# FuseBox_ECU_R3.net
KiCad netlist of a schematic drawn in EAGLE
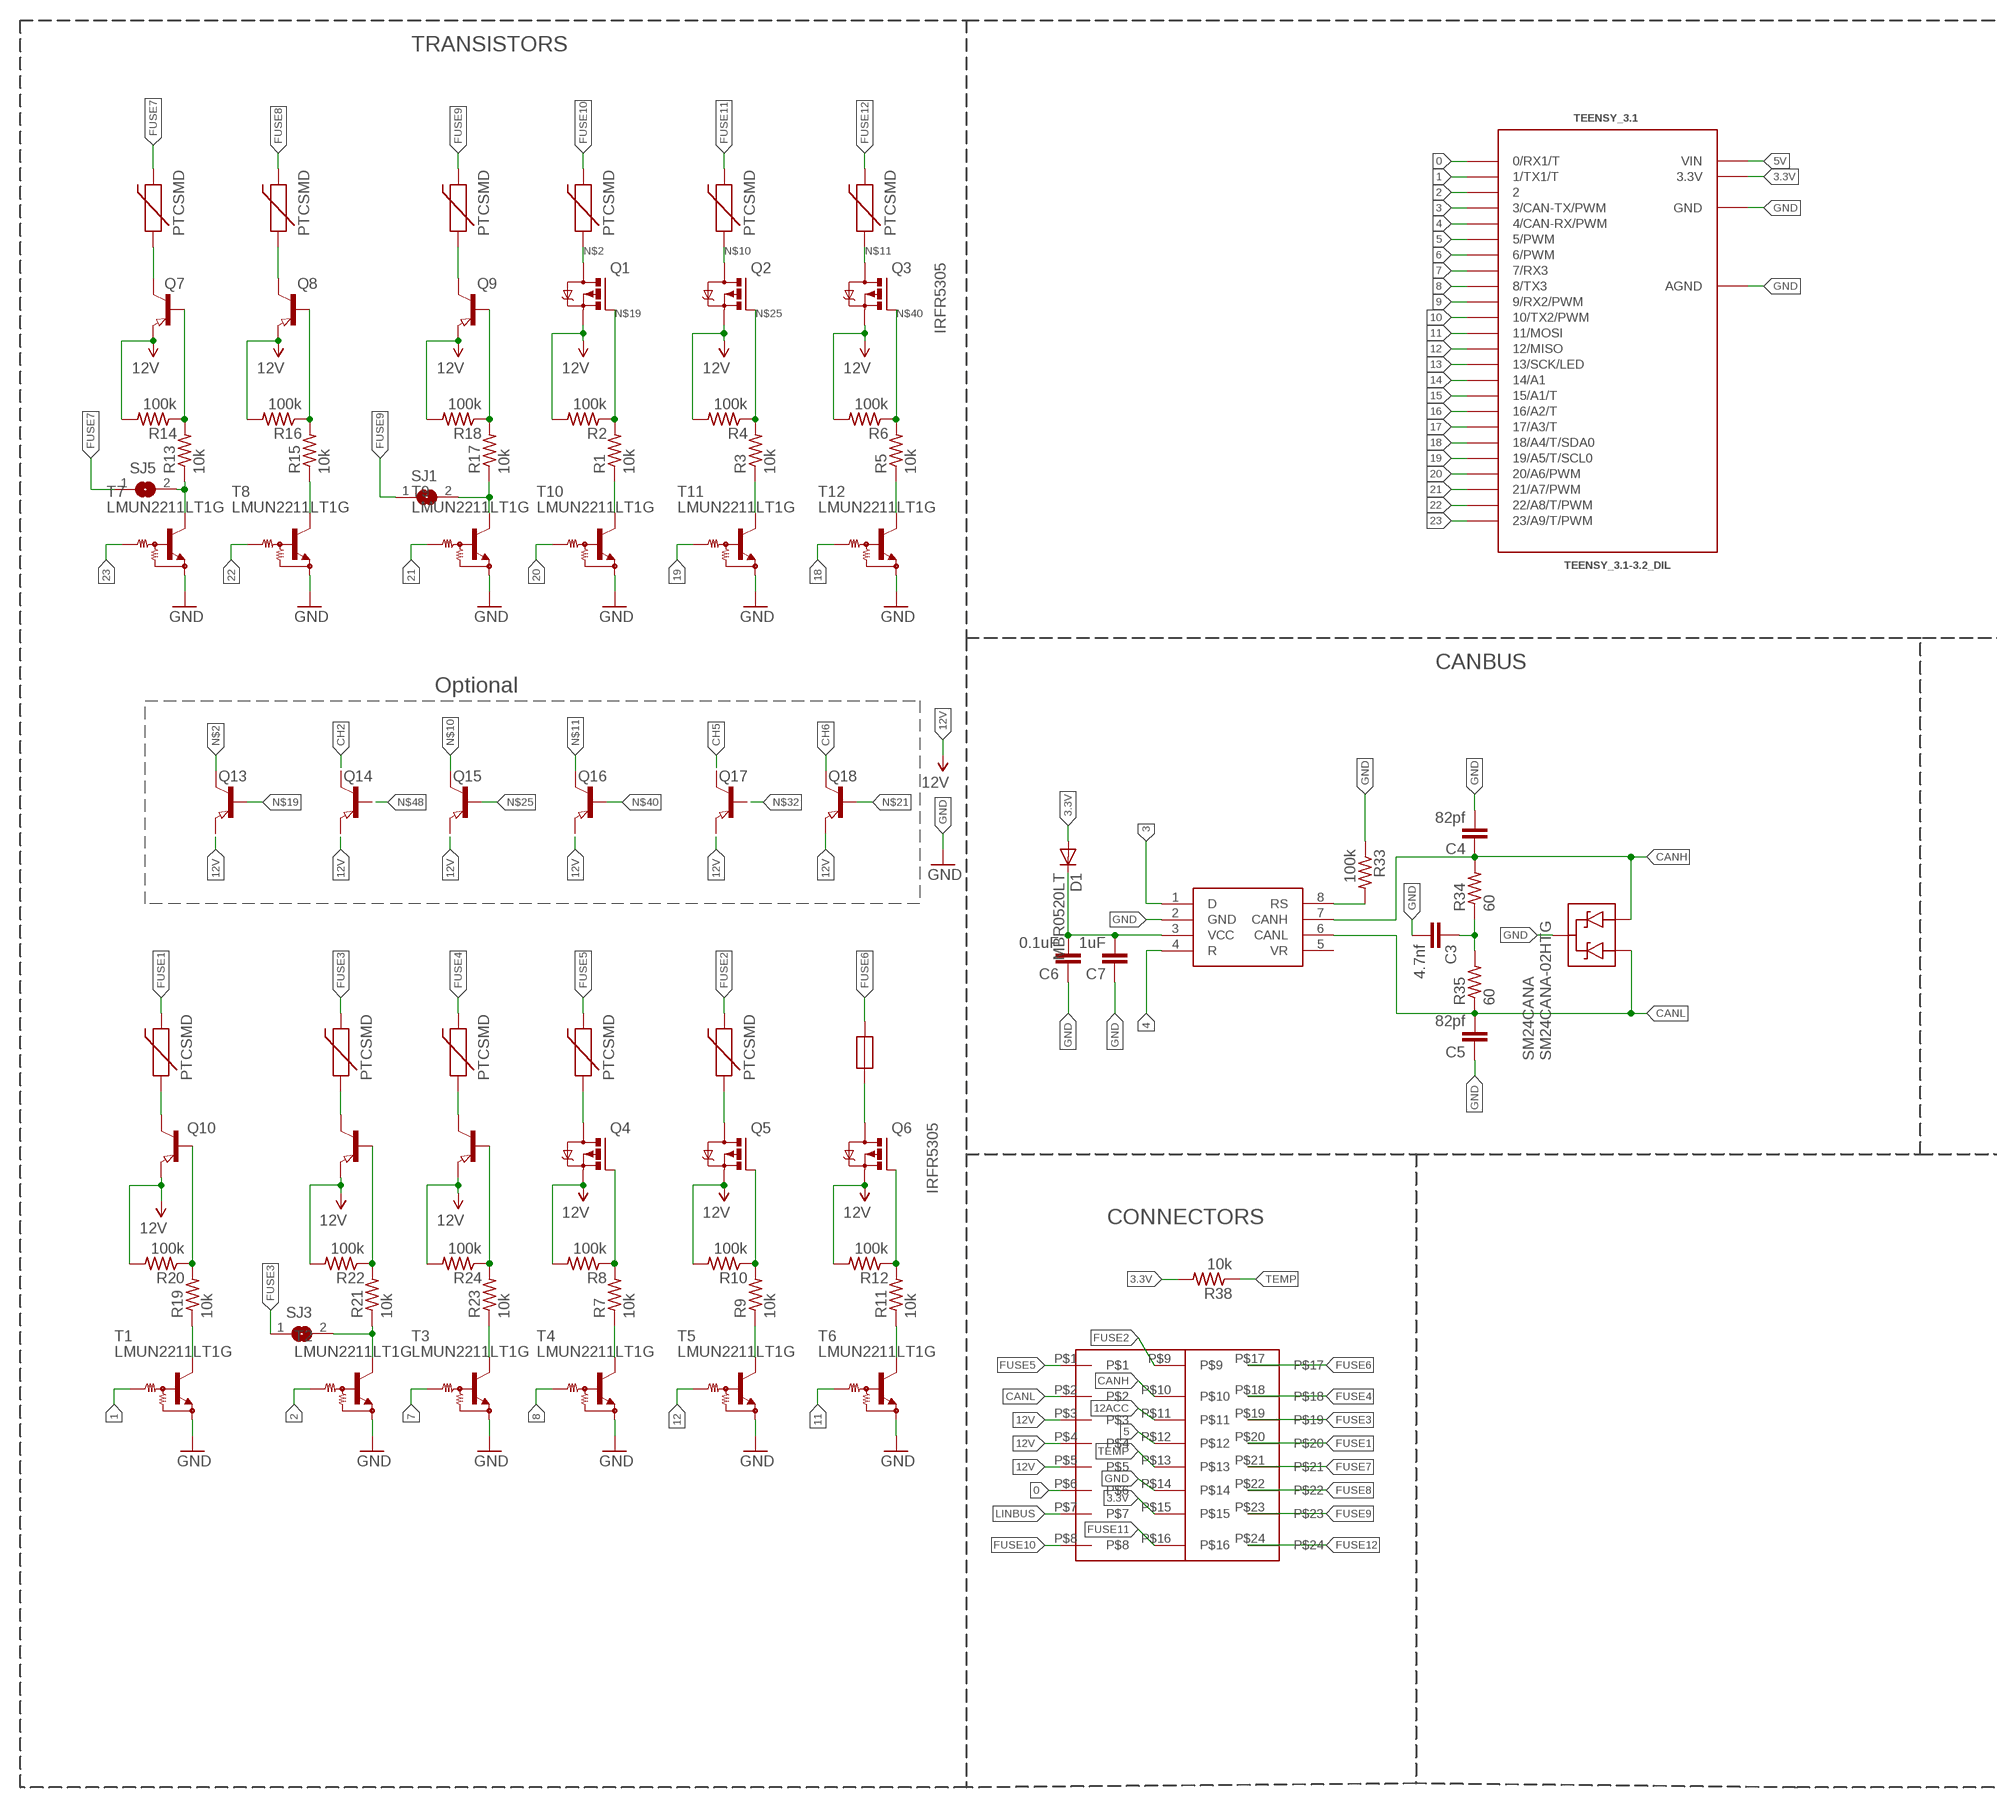
[diagram p0: schematic, sheet 1, part 1 of 2]
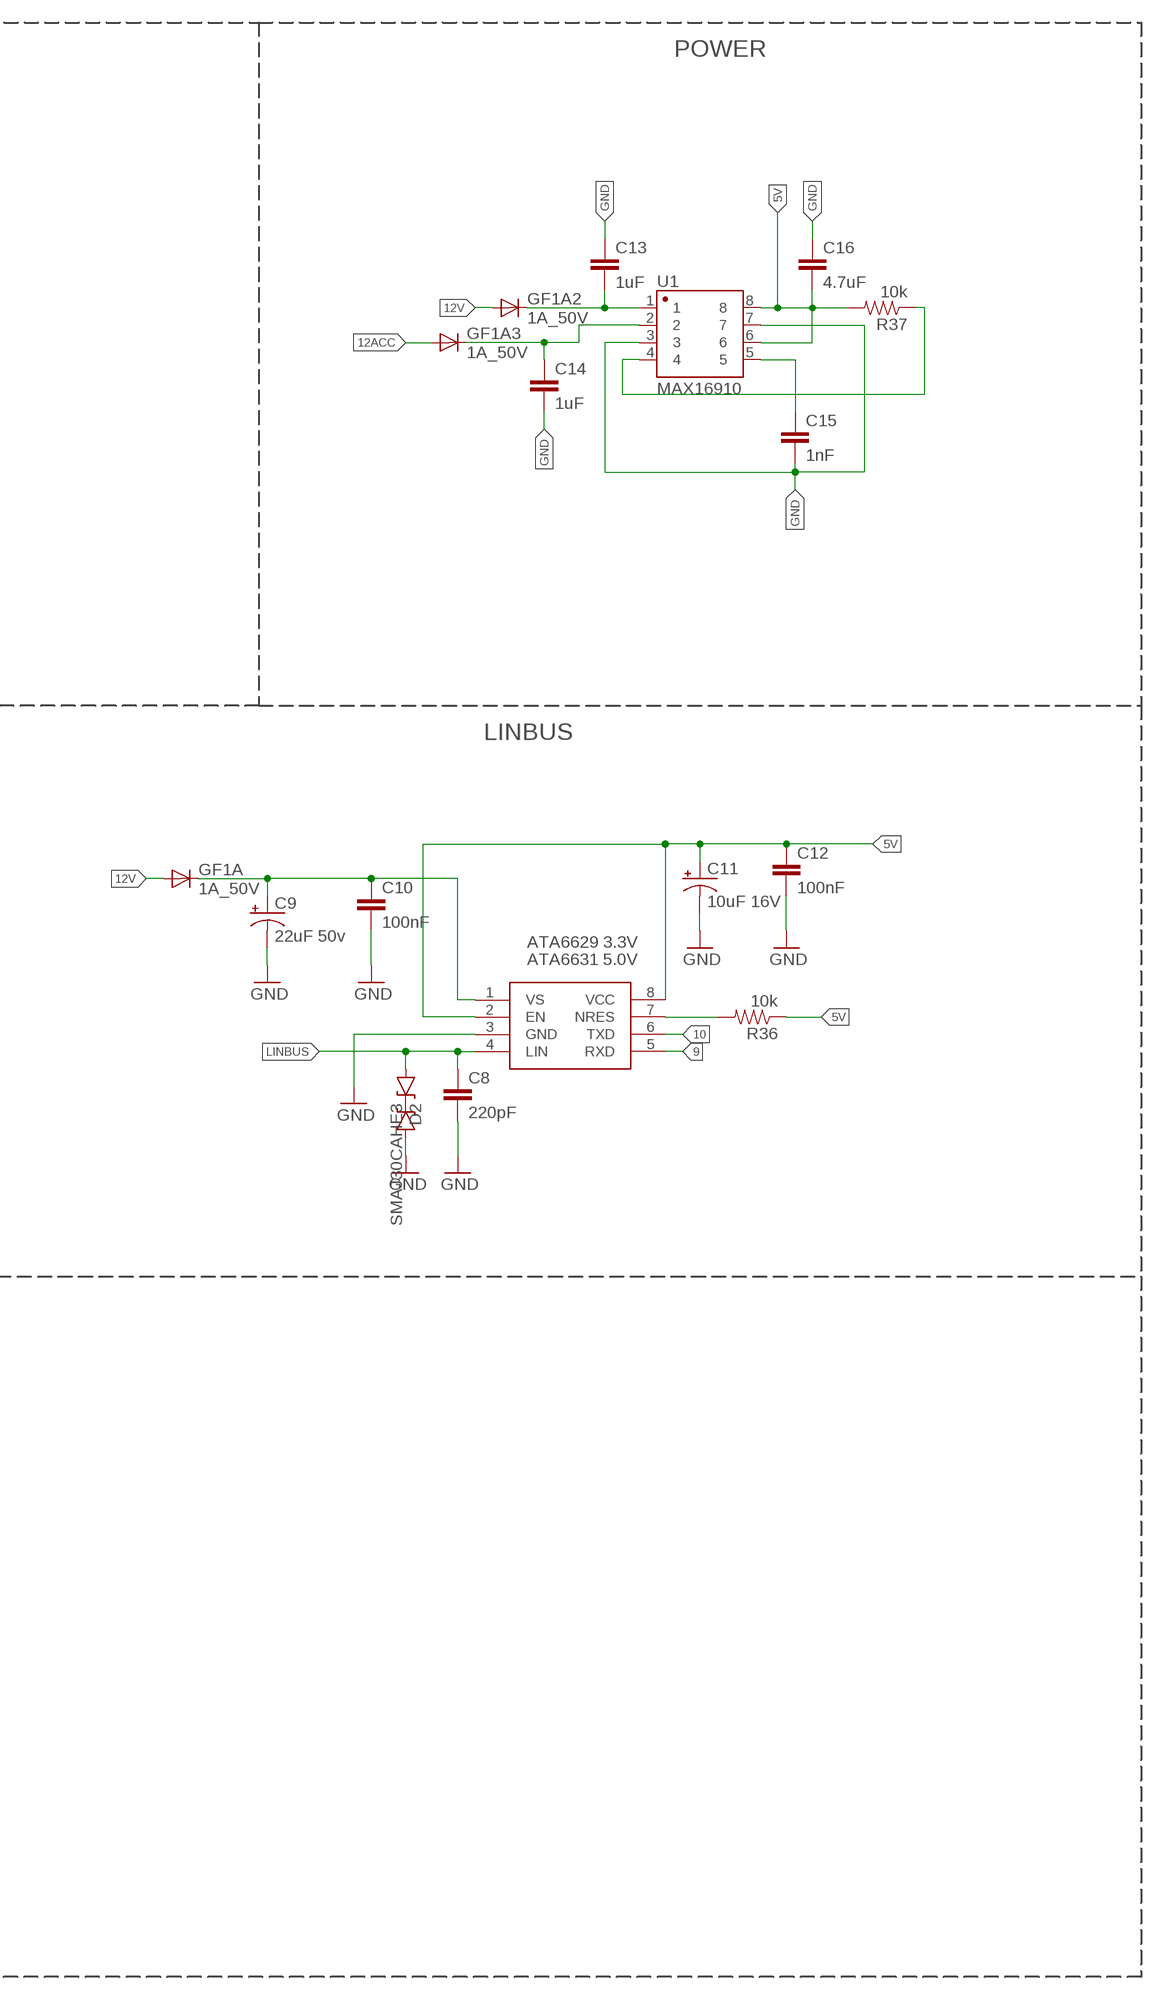
[diagram p1: schematic, sheet 1, part 2 of 2]

(export (version "E")
  (design (tool "Eeschema 10.0.6"))
  (components
    (comp (ref "ATA6631")
      (value "ATA6631")
      (footprint "eagle-import:S08")
      (libsource (lib "eagle-import") (part "ATA6631"))
    )
    (comp (ref "C3")
      (value "4.7nf")
      (footprint "eagle-import:0603-CAP")
      (libsource (lib "eagle-import") (part "SparkFun-Capacitors_CAP0603-CAP"))
    )
    (comp (ref "C4")
      (value "82pf")
      (footprint "eagle-import:0603-CAP")
      (libsource (lib "eagle-import") (part "SparkFun-Capacitors_CAP0603-CAP"))
    )
    (comp (ref "C5")
      (value "82pf")
      (footprint "eagle-import:0603-CAP")
      (libsource (lib "eagle-import") (part "SparkFun-Capacitors_CAP0603-CAP"))
    )
    (comp (ref "C6")
      (value "0.1uF")
      (footprint "eagle-import:0603-CAP")
      (libsource (lib "eagle-import") (part "SparkFun-Capacitors_CAP0603-CAP"))
    )
    (comp (ref "C7")
      (value "1uF")
      (footprint "eagle-import:0603-CAP")
      (libsource (lib "eagle-import") (part "SparkFun-Capacitors_CAP0603-CAP"))
    )
    (comp (ref "C8")
      (value "220pF")
      (footprint "eagle-import:0603-CAP")
      (libsource (lib "eagle-import") (part "SparkFun-Capacitors_CAP0603-CAP"))
    )
    (comp (ref "C9")
      (value "22uF 50v")
      (footprint "eagle-import:PANASONIC_D")
      (libsource (lib "eagle-import") (part "SparkFun-Capacitors_CAP_POLD"))
    )
    (comp (ref "C10")
      (value "100nF")
      (footprint "eagle-import:0603-CAP")
      (libsource (lib "eagle-import") (part "SparkFun-Capacitors_CAP0603-CAP"))
    )
    (comp (ref "C11")
      (value "10uF 16V")
      (footprint "eagle-import:EIA3216")
      (libsource (lib "eagle-import") (part "CAP_POL1206"))
    )
    (comp (ref "C12")
      (value "100nF")
      (footprint "eagle-import:0603-CAP")
      (libsource (lib "eagle-import") (part "SparkFun-Capacitors_CAP0603-CAP"))
    )
    (comp (ref "C13")
      (value "1uF")
      (footprint "eagle-import:0805")
      (libsource (lib "eagle-import") (part "CAP0805"))
    )
    (comp (ref "C14")
      (value "1uF")
      (footprint "eagle-import:0805")
      (libsource (lib "eagle-import") (part "CAP0805"))
    )
    (comp (ref "C15")
      (value "1nF")
      (footprint "eagle-import:0805")
      (libsource (lib "eagle-import") (part "CAP0805"))
    )
    (comp (ref "C16")
      (value "4.7uF")
      (footprint "eagle-import:0805")
      (libsource (lib "eagle-import") (part "CAP0805"))
    )
    (comp (ref "D1")
      (value "MBR0520LT")
      (footprint "eagle-import:SOD123")
      (libsource (lib "eagle-import") (part "MBR0520LT"))
    )
    (comp (ref "D2")
      (value "SMAJ30CAHE3")
      (footprint "eagle-import:SMA-DIODE")
      (libsource (lib "eagle-import") (part "SMAJ30CAHE3"))
    )
    (comp (ref "F1")
      (value "PTCSMD")
      (footprint "eagle-import:PTC-1206")
      (libsource (lib "eagle-import") (part "PTCSMD"))
    )
    (comp (ref "F2")
      (value "PTCSMD")
      (footprint "eagle-import:PTC-1206")
      (libsource (lib "eagle-import") (part "PTCSMD"))
    )
    (comp (ref "F3")
      (value "PTCSMD")
      (footprint "eagle-import:PTC-1206")
      (libsource (lib "eagle-import") (part "PTCSMD"))
    )
    (comp (ref "F4")
      (value "PTCSMD")
      (footprint "eagle-import:PTC-1206")
      (libsource (lib "eagle-import") (part "PTCSMD"))
    )
    (comp (ref "F5")
      (value "PTCSMD")
      (footprint "eagle-import:PTC-1206")
      (libsource (lib "eagle-import") (part "PTCSMD"))
    )
    (comp (ref "F6")
      (value "PTCSMD")
      (footprint "eagle-import:PTC-1206")
      (libsource (lib "eagle-import") (part "PTCSMD"))
    )
    (comp (ref "F7")
      (value "PTCSMD")
      (footprint "eagle-import:PTC-1206")
      (libsource (lib "eagle-import") (part "PTCSMD"))
    )
    (comp (ref "F8")
      (value "PTCSMD")
      (footprint "eagle-import:PTC-1206")
      (libsource (lib "eagle-import") (part "PTCSMD"))
    )
    (comp (ref "F9")
      (value "PTCSMD")
      (footprint "eagle-import:PTC-1206")
      (libsource (lib "eagle-import") (part "PTCSMD"))
    )
    (comp (ref "F10")
      (value "PTCSMD")
      (footprint "eagle-import:PTC-1206")
      (libsource (lib "eagle-import") (part "PTCSMD"))
    )
    (comp (ref "F11")
      (value "PTCSMD")
      (footprint "eagle-import:PTC-1206")
      (libsource (lib "eagle-import") (part "PTCSMD"))
    )
    (comp (ref "GF1A")
      (value "1A_50V")
      (footprint "eagle-import:DO-214AC")
      (libsource (lib "eagle-import") (part "DIODE-DO-214AC"))
    )
    (comp (ref "GF1A2")
      (value "1A_50V")
      (footprint "eagle-import:DO-214AC")
      (libsource (lib "eagle-import") (part "DIODE-DO-214AC"))
    )
    (comp (ref "GF1A3")
      (value "1A_50V")
      (footprint "eagle-import:DO-214AC")
      (libsource (lib "eagle-import") (part "DIODE-DO-214AC"))
    )
    (comp (ref "Q1")
      (value "IRFR5305")
      (footprint "eagle-import:D-PAK_TO252AA")
      (libsource (lib "eagle-import") (part "IRF?5305R"))
    )
    (comp (ref "Q2")
      (value "IRFR5305")
      (footprint "eagle-import:D-PAK_TO252AA")
      (libsource (lib "eagle-import") (part "IRF?5305R"))
    )
    (comp (ref "Q3")
      (value "IRFR5305")
      (footprint "eagle-import:D-PAK_TO252AA")
      (libsource (lib "eagle-import") (part "IRF?5305R"))
    )
    (comp (ref "Q4")
      (value "IRFR5305")
      (footprint "eagle-import:D-PAK_TO252AA")
      (libsource (lib "eagle-import") (part "IRF?5305R"))
    )
    (comp (ref "Q5")
      (value "IRFR5305")
      (footprint "eagle-import:D-PAK_TO252AA")
      (libsource (lib "eagle-import") (part "IRF?5305R"))
    )
    (comp (ref "Q6")
      (value "IRFR5305")
      (footprint "eagle-import:D-PAK_TO252AA")
      (libsource (lib "eagle-import") (part "IRF?5305R"))
    )
    (comp (ref "Q7")
      (value "PNP-TRANSISTOR_SOT23")
      (footprint "eagle-import:SOT23")
      (libsource (lib "eagle-import") (part "PNP-TRANSISTOR_SOT23"))
    )
    (comp (ref "Q8")
      (value "PNP-TRANSISTOR_SOT23")
      (footprint "eagle-import:SOT23")
      (libsource (lib "eagle-import") (part "PNP-TRANSISTOR_SOT23"))
    )
    (comp (ref "Q9")
      (value "PNP-TRANSISTOR_SOT23")
      (footprint "eagle-import:SOT23")
      (libsource (lib "eagle-import") (part "PNP-TRANSISTOR_SOT23"))
    )
    (comp (ref "Q10")
      (value "PNP-TRANSISTOR_SOT23")
      (footprint "eagle-import:SOT23")
      (libsource (lib "eagle-import") (part "PNP-TRANSISTOR_SOT23"))
    )
    (comp (ref "Q11")
      (value "PNP-TRANSISTOR_SOT23")
      (footprint "eagle-import:SOT23")
      (libsource (lib "eagle-import") (part "PNP-TRANSISTOR_SOT23"))
    )
    (comp (ref "Q12")
      (value "PNP-TRANSISTOR_SOT23")
      (footprint "eagle-import:SOT23")
      (libsource (lib "eagle-import") (part "PNP-TRANSISTOR_SOT23"))
    )
    (comp (ref "Q13")
      (value "PNP-TRANSISTOR_SOT23")
      (footprint "eagle-import:SOT23")
      (libsource (lib "eagle-import") (part "PNP-TRANSISTOR_SOT23"))
    )
    (comp (ref "Q14")
      (value "PNP-TRANSISTOR_SOT23")
      (footprint "eagle-import:SOT23")
      (libsource (lib "eagle-import") (part "PNP-TRANSISTOR_SOT23"))
    )
    (comp (ref "Q15")
      (value "PNP-TRANSISTOR_SOT23")
      (footprint "eagle-import:SOT23")
      (libsource (lib "eagle-import") (part "PNP-TRANSISTOR_SOT23"))
    )
    (comp (ref "Q16")
      (value "PNP-TRANSISTOR_SOT23")
      (footprint "eagle-import:SOT23")
      (libsource (lib "eagle-import") (part "PNP-TRANSISTOR_SOT23"))
    )
    (comp (ref "Q17")
      (value "PNP-TRANSISTOR_SOT23")
      (footprint "eagle-import:SOT23")
      (libsource (lib "eagle-import") (part "PNP-TRANSISTOR_SOT23"))
    )
    (comp (ref "Q18")
      (value "PNP-TRANSISTOR_SOT23")
      (footprint "eagle-import:SOT23")
      (libsource (lib "eagle-import") (part "PNP-TRANSISTOR_SOT23"))
    )
    (comp (ref "R1")
      (value "10k")
      (footprint "eagle-import:R0402")
      (libsource (lib "eagle-import") (part "R-US_R0402"))
    )
    (comp (ref "R2")
      (value "100k")
      (footprint "eagle-import:R0402")
      (libsource (lib "eagle-import") (part "R-US_R0402"))
    )
    (comp (ref "R3")
      (value "10k")
      (footprint "eagle-import:R0402")
      (libsource (lib "eagle-import") (part "R-US_R0402"))
    )
    (comp (ref "R4")
      (value "100k")
      (footprint "eagle-import:R0402")
      (libsource (lib "eagle-import") (part "R-US_R0402"))
    )
    (comp (ref "R5")
      (value "10k")
      (footprint "eagle-import:R0402")
      (libsource (lib "eagle-import") (part "R-US_R0402"))
    )
    (comp (ref "R6")
      (value "100k")
      (footprint "eagle-import:R0402")
      (libsource (lib "eagle-import") (part "R-US_R0402"))
    )
    (comp (ref "R7")
      (value "10k")
      (footprint "eagle-import:R0402")
      (libsource (lib "eagle-import") (part "R-US_R0402"))
    )
    (comp (ref "R8")
      (value "100k")
      (footprint "eagle-import:R0402")
      (libsource (lib "eagle-import") (part "R-US_R0402"))
    )
    (comp (ref "R9")
      (value "10k")
      (footprint "eagle-import:R0402")
      (libsource (lib "eagle-import") (part "R-US_R0402"))
    )
    (comp (ref "R10")
      (value "100k")
      (footprint "eagle-import:R0402")
      (libsource (lib "eagle-import") (part "R-US_R0402"))
    )
    (comp (ref "R11")
      (value "10k")
      (footprint "eagle-import:R0402")
      (libsource (lib "eagle-import") (part "R-US_R0402"))
    )
    (comp (ref "R12")
      (value "100k")
      (footprint "eagle-import:R0402")
      (libsource (lib "eagle-import") (part "R-US_R0402"))
    )
    (comp (ref "R13")
      (value "10k")
      (footprint "eagle-import:R0402")
      (libsource (lib "eagle-import") (part "R-US_R0402"))
    )
    (comp (ref "R14")
      (value "100k")
      (footprint "eagle-import:R0402")
      (libsource (lib "eagle-import") (part "R-US_R0402"))
    )
    (comp (ref "R15")
      (value "10k")
      (footprint "eagle-import:R0402")
      (libsource (lib "eagle-import") (part "R-US_R0402"))
    )
    (comp (ref "R16")
      (value "100k")
      (footprint "eagle-import:R0402")
      (libsource (lib "eagle-import") (part "R-US_R0402"))
    )
    (comp (ref "R17")
      (value "10k")
      (footprint "eagle-import:R0402")
      (libsource (lib "eagle-import") (part "R-US_R0402"))
    )
    (comp (ref "R18")
      (value "100k")
      (footprint "eagle-import:R0402")
      (libsource (lib "eagle-import") (part "R-US_R0402"))
    )
    (comp (ref "R19")
      (value "10k")
      (footprint "eagle-import:R0402")
      (libsource (lib "eagle-import") (part "R-US_R0402"))
    )
    (comp (ref "R20")
      (value "100k")
      (footprint "eagle-import:R0402")
      (libsource (lib "eagle-import") (part "R-US_R0402"))
    )
    (comp (ref "R21")
      (value "10k")
      (footprint "eagle-import:R0402")
      (libsource (lib "eagle-import") (part "R-US_R0402"))
    )
    (comp (ref "R22")
      (value "100k")
      (footprint "eagle-import:R0402")
      (libsource (lib "eagle-import") (part "R-US_R0402"))
    )
    (comp (ref "R23")
      (value "10k")
      (footprint "eagle-import:R0402")
      (libsource (lib "eagle-import") (part "R-US_R0402"))
    )
    (comp (ref "R24")
      (value "100k")
      (footprint "eagle-import:R0402")
      (libsource (lib "eagle-import") (part "R-US_R0402"))
    )
    (comp (ref "R33")
      (value "100k")
      (footprint "eagle-import:R0402")
      (libsource (lib "eagle-import") (part "R-US_R0402"))
    )
    (comp (ref "R34")
      (value "60")
      (footprint "eagle-import:R0402")
      (libsource (lib "eagle-import") (part "R-US_R0402"))
    )
    (comp (ref "R35")
      (value "60")
      (footprint "eagle-import:R0402")
      (libsource (lib "eagle-import") (part "R-US_R0402"))
    )
    (comp (ref "R36")
      (value "10k")
      (footprint "eagle-import:0603-RES")
      (libsource (lib "eagle-import") (part "RESISTOR0603-RES"))
    )
    (comp (ref "R37")
      (value "10k")
      (footprint "eagle-import:0603-RES")
      (libsource (lib "eagle-import") (part "RESISTOR0603-RES"))
    )
    (comp (ref "R38")
      (value "10k")
      (footprint "eagle-import:R0402")
      (libsource (lib "eagle-import") (part "R-US_R0402"))
    )
    (comp (ref "SJ1") (value "SJ") (footprint "eagle-import:SJ") (libsource (lib "eagle-import") (part "SJ")))
    (comp (ref "SJ3") (value "SJ") (footprint "eagle-import:SJ") (libsource (lib "eagle-import") (part "SJ")))
    (comp (ref "SJ5") (value "SJ") (footprint "eagle-import:SJ") (libsource (lib "eagle-import") (part "SJ")))
    (comp (ref "SM24CANA")
      (value "SM24CANA-02HTG")
      (footprint "eagle-import:SOT23-3")
      (libsource (lib "eagle-import") (part "MMBZ27VCLT1"))
    )
    (comp (ref "T1")
      (value "LMUN2211LT1G")
      (footprint "eagle-import:SOT23")
      (libsource (lib "eagle-import") (part "LMUN2211LT1G"))
    )
    (comp (ref "T2")
      (value "LMUN2211LT1G")
      (footprint "eagle-import:SOT23")
      (libsource (lib "eagle-import") (part "LMUN2211LT1G"))
    )
    (comp (ref "T3")
      (value "LMUN2211LT1G")
      (footprint "eagle-import:SOT23")
      (libsource (lib "eagle-import") (part "LMUN2211LT1G"))
    )
    (comp (ref "T4")
      (value "LMUN2211LT1G")
      (footprint "eagle-import:SOT23")
      (libsource (lib "eagle-import") (part "LMUN2211LT1G"))
    )
    (comp (ref "T5")
      (value "LMUN2211LT1G")
      (footprint "eagle-import:SOT23")
      (libsource (lib "eagle-import") (part "LMUN2211LT1G"))
    )
    (comp (ref "T6")
      (value "LMUN2211LT1G")
      (footprint "eagle-import:SOT23")
      (libsource (lib "eagle-import") (part "LMUN2211LT1G"))
    )
    (comp (ref "T7")
      (value "LMUN2211LT1G")
      (footprint "eagle-import:SOT23")
      (libsource (lib "eagle-import") (part "LMUN2211LT1G"))
    )
    (comp (ref "T8")
      (value "LMUN2211LT1G")
      (footprint "eagle-import:SOT23")
      (libsource (lib "eagle-import") (part "LMUN2211LT1G"))
    )
    (comp (ref "T9")
      (value "LMUN2211LT1G")
      (footprint "eagle-import:SOT23")
      (libsource (lib "eagle-import") (part "LMUN2211LT1G"))
    )
    (comp (ref "T10")
      (value "LMUN2211LT1G")
      (footprint "eagle-import:SOT23")
      (libsource (lib "eagle-import") (part "LMUN2211LT1G"))
    )
    (comp (ref "T11")
      (value "LMUN2211LT1G")
      (footprint "eagle-import:SOT23")
      (libsource (lib "eagle-import") (part "LMUN2211LT1G"))
    )
    (comp (ref "T12")
      (value "LMUN2211LT1G")
      (footprint "eagle-import:SOT23")
      (libsource (lib "eagle-import") (part "LMUN2211LT1G"))
    )
    (comp (ref "TEENSY_3.1")
      (value "TEENSY_3.1-3.2_DIL")
      (footprint "eagle-import:TEENSY_3.0-3.2&LC_DIL")
      (libsource (lib "eagle-import") (part "TEENSY_3.1-3.2_DIL"))
    )
    (comp (ref "U$2")
      (value "RESETTABLE_1210")
      (footprint "eagle-import:1210")
      (libsource (lib "eagle-import") (part "RESETTABLE_1210"))
    )
    (comp (ref "U$3")
      (value "HCCPHPE24BKA90F")
      (footprint "eagle-import:HCCPHPE24BKA90F")
      (libsource (lib "eagle-import") (part "HCCPHPE24BKA90F"))
    )
    (comp (ref "U1")
      (value "MAX16910")
      (footprint "eagle-import:SO08")
      (libsource (lib "eagle-import") (part "GENERIC-SOIC8MSGEQ7N-FILTER"))
    )
    (comp (ref "VP230")
      (value "UP230")
      (footprint "eagle-import:SO08")
      (libsource (lib "eagle-import") (part "SN65HVD230"))
    )
  )
  (nets
    (net (code "1") (name "0") (class "Default")
      (node (ref "TEENSY_3.1") (pin "0") (pinfunction "0/RX1/T_0") (pintype "bidirectional"))
      (node (ref "U$3") (pin "P$6") (pinfunction "P$6_P$6") (pintype "bidirectional"))
    )
    (net (code "2") (name "1") (class "Default")
      (node (ref "T1") (pin "1") (pinfunction "B_1") (pintype "passive"))
      (node (ref "TEENSY_3.1") (pin "1") (pinfunction "1/TX1/T_1") (pintype "bidirectional"))
    )
    (net (code "3") (name "2") (class "Default")
      (node (ref "T2") (pin "1") (pinfunction "B_1") (pintype "passive"))
      (node (ref "TEENSY_3.1") (pin "2") (pinfunction "2_2") (pintype "bidirectional"))
    )
    (net (code "4") (name "3") (class "Default")
      (node (ref "TEENSY_3.1") (pin "3") (pinfunction "3/CAN-TX/PWM_3") (pintype "bidirectional"))
      (node (ref "VP230") (pin "1") (pinfunction "D_1") (pintype "bidirectional"))
    )
    (net (code "5") (name "3.3V") (class "Default")
      (node (ref "D1") (pin "A") (pinfunction "A_A") (pintype "passive"))
      (node (ref "R38") (pin "2") (pinfunction "2_2") (pintype "passive"))
      (node (ref "TEENSY_3.1") (pin "3.3V") (pinfunction "3.3V_3.3V") (pintype "power_in"))
      (node (ref "U$3") (pin "P$15") (pinfunction "P$15_P$15") (pintype "bidirectional"))
    )
    (net (code "6") (name "4") (class "Default")
      (node (ref "TEENSY_3.1") (pin "4") (pinfunction "4/CAN-RX/PWM_4") (pintype "bidirectional"))
      (node (ref "VP230") (pin "4") (pinfunction "R_4") (pintype "bidirectional"))
    )
    (net (code "7") (name "5") (class "Default")
      (node (ref "TEENSY_3.1") (pin "5") (pinfunction "5/PWM_5") (pintype "bidirectional"))
      (node (ref "U$3") (pin "P$12") (pinfunction "P$12_P$12") (pintype "bidirectional"))
    )
    (net (code "8") (name "5V") (class "Default")
      (node (ref "ATA6631") (pin "2") (pinfunction "EN_2") (pintype "bidirectional"))
      (node (ref "ATA6631") (pin "8") (pinfunction "VCC_8") (pintype "bidirectional"))
      (node (ref "C11") (pin "A") (pinfunction "+_A") (pintype "passive"))
      (node (ref "C12") (pin "1") (pinfunction "1_1") (pintype "passive"))
      (node (ref "C16") (pin "2") (pinfunction "2_2") (pintype "passive"))
      (node (ref "R36") (pin "1") (pinfunction "1_1") (pintype "passive"))
      (node (ref "R37") (pin "2") (pinfunction "2_2") (pintype "passive"))
      (node (ref "TEENSY_3.1") (pin "VIN") (pinfunction "VIN_VIN") (pintype "power_in"))
      (node (ref "U1") (pin "6") (pinfunction "6_6") (pintype "bidirectional"))
      (node (ref "U1") (pin "8") (pinfunction "8_8") (pintype "bidirectional"))
    )
    (net (code "9") (name "6") (class "Default")
      (node (ref "TEENSY_3.1") (pin "6") (pinfunction "6/PWM_6") (pintype "bidirectional"))
    )
    (net (code "10") (name "7") (class "Default")
      (node (ref "T3") (pin "1") (pinfunction "B_1") (pintype "passive"))
      (node (ref "TEENSY_3.1") (pin "7") (pinfunction "7/RX3_7") (pintype "bidirectional"))
    )
    (net (code "11") (name "8") (class "Default")
      (node (ref "T4") (pin "1") (pinfunction "B_1") (pintype "passive"))
      (node (ref "TEENSY_3.1") (pin "8") (pinfunction "8/TX3_8") (pintype "bidirectional"))
    )
    (net (code "12") (name "9") (class "Default")
      (node (ref "ATA6631") (pin "5") (pinfunction "RXD_5") (pintype "bidirectional"))
      (node (ref "TEENSY_3.1") (pin "9") (pinfunction "9/RX2/PWM_9") (pintype "bidirectional"))
    )
    (net (code "13") (name "10") (class "Default")
      (node (ref "ATA6631") (pin "6") (pinfunction "TXD_6") (pintype "bidirectional"))
      (node (ref "TEENSY_3.1") (pin "10") (pinfunction "10/TX2/PWM_10") (pintype "bidirectional"))
    )
    (net (code "14") (name "11") (class "Default")
      (node (ref "T6") (pin "1") (pinfunction "B_1") (pintype "passive"))
      (node (ref "TEENSY_3.1") (pin "11") (pinfunction "11/MOSI_11") (pintype "bidirectional"))
    )
    (net (code "15") (name "12") (class "Default")
      (node (ref "T5") (pin "1") (pinfunction "B_1") (pintype "passive"))
      (node (ref "TEENSY_3.1") (pin "12") (pinfunction "12/MISO_12") (pintype "bidirectional"))
    )
    (net (code "16") (name "12ACC") (class "Default")
      (node (ref "GF1A3") (pin "A") (pinfunction "A_A") (pintype "passive"))
      (node (ref "U$3") (pin "P$11") (pinfunction "P$11_P$11") (pintype "bidirectional"))
    )
    (net (code "17") (name "12V") (class "Default")
      (node (ref "GF1A") (pin "A") (pinfunction "A_A") (pintype "passive"))
      (node (ref "GF1A2") (pin "A") (pinfunction "A_A") (pintype "passive"))
      (node (ref "Q1") (pin "3") (pinfunction "S_3") (pintype "passive"))
      (node (ref "Q10") (pin "2") (pinfunction "E_2") (pintype "passive"))
      (node (ref "Q11") (pin "2") (pinfunction "E_2") (pintype "passive"))
      (node (ref "Q12") (pin "2") (pinfunction "E_2") (pintype "passive"))
      (node (ref "Q13") (pin "2") (pinfunction "E_2") (pintype "passive"))
      (node (ref "Q14") (pin "2") (pinfunction "E_2") (pintype "passive"))
      (node (ref "Q15") (pin "2") (pinfunction "E_2") (pintype "passive"))
      (node (ref "Q16") (pin "2") (pinfunction "E_2") (pintype "passive"))
      (node (ref "Q17") (pin "2") (pinfunction "E_2") (pintype "passive"))
      (node (ref "Q18") (pin "2") (pinfunction "E_2") (pintype "passive"))
      (node (ref "Q2") (pin "3") (pinfunction "S_3") (pintype "passive"))
      (node (ref "Q3") (pin "3") (pinfunction "S_3") (pintype "passive"))
      (node (ref "Q4") (pin "3") (pinfunction "S_3") (pintype "passive"))
      (node (ref "Q5") (pin "3") (pinfunction "S_3") (pintype "passive"))
      (node (ref "Q6") (pin "3") (pinfunction "S_3") (pintype "passive"))
      (node (ref "Q7") (pin "2") (pinfunction "E_2") (pintype "passive"))
      (node (ref "Q8") (pin "2") (pinfunction "E_2") (pintype "passive"))
      (node (ref "Q9") (pin "2") (pinfunction "E_2") (pintype "passive"))
      (node (ref "R10") (pin "2") (pinfunction "2_2") (pintype "passive"))
      (node (ref "R12") (pin "2") (pinfunction "2_2") (pintype "passive"))
      (node (ref "R14") (pin "2") (pinfunction "2_2") (pintype "passive"))
      (node (ref "R16") (pin "2") (pinfunction "2_2") (pintype "passive"))
      (node (ref "R18") (pin "2") (pinfunction "2_2") (pintype "passive"))
      (node (ref "R2") (pin "2") (pinfunction "2_2") (pintype "passive"))
      (node (ref "R20") (pin "2") (pinfunction "2_2") (pintype "passive"))
      (node (ref "R22") (pin "2") (pinfunction "2_2") (pintype "passive"))
      (node (ref "R24") (pin "2") (pinfunction "2_2") (pintype "passive"))
      (node (ref "R4") (pin "2") (pinfunction "2_2") (pintype "passive"))
      (node (ref "R6") (pin "2") (pinfunction "2_2") (pintype "passive"))
      (node (ref "R8") (pin "2") (pinfunction "2_2") (pintype "passive"))
      (node (ref "U$3") (pin "P$3") (pinfunction "P$3_P$3") (pintype "bidirectional"))
      (node (ref "U$3") (pin "P$4") (pinfunction "P$4_P$4") (pintype "bidirectional"))
      (node (ref "U$3") (pin "P$5") (pinfunction "P$5_P$5") (pintype "bidirectional"))
    )
    (net (code "18") (name "13") (class "Default")
      (node (ref "TEENSY_3.1") (pin "13") (pinfunction "13/SCK/LED_13") (pintype "bidirectional"))
    )
    (net (code "19") (name "14") (class "Default")
      (node (ref "TEENSY_3.1") (pin "14/A0") (pinfunction "14/A1_14/A0") (pintype "bidirectional"))
    )
    (net (code "20") (name "15") (class "Default")
      (node (ref "TEENSY_3.1") (pin "15/A1") (pinfunction "15/A1/T_15/A1") (pintype "bidirectional"))
    )
    (net (code "21") (name "16") (class "Default")
      (node (ref "TEENSY_3.1") (pin "16/A2") (pinfunction "16/A2/T_16/A2") (pintype "bidirectional"))
    )
    (net (code "22") (name "17") (class "Default")
      (node (ref "TEENSY_3.1") (pin "17/A3") (pinfunction "17/A3/T_17/A3") (pintype "bidirectional"))
    )
    (net (code "23") (name "18") (class "Default")
      (node (ref "T12") (pin "1") (pinfunction "B_1") (pintype "passive"))
      (node (ref "TEENSY_3.1") (pin "18/A4") (pinfunction "18/A4/T/SDA0_18/A4") (pintype "bidirectional"))
    )
    (net (code "24") (name "19") (class "Default")
      (node (ref "T11") (pin "1") (pinfunction "B_1") (pintype "passive"))
      (node (ref "TEENSY_3.1") (pin "19/A5") (pinfunction "19/A5/T/SCL0_19/A5") (pintype "bidirectional"))
    )
    (net (code "25") (name "20") (class "Default")
      (node (ref "T10") (pin "1") (pinfunction "B_1") (pintype "passive"))
      (node (ref "TEENSY_3.1") (pin "20/A6") (pinfunction "20/A6/PWM_20/A6") (pintype "bidirectional"))
    )
    (net (code "26") (name "21") (class "Default")
      (node (ref "T9") (pin "1") (pinfunction "B_1") (pintype "passive"))
      (node (ref "TEENSY_3.1") (pin "21/A7") (pinfunction "21/A7/PWM_21/A7") (pintype "bidirectional"))
    )
    (net (code "27") (name "22") (class "Default")
      (node (ref "T8") (pin "1") (pinfunction "B_1") (pintype "passive"))
      (node (ref "TEENSY_3.1") (pin "22/A8") (pinfunction "22/A8/T/PWM_22/A8") (pintype "bidirectional"))
    )
    (net (code "28") (name "23") (class "Default")
      (node (ref "T7") (pin "1") (pinfunction "B_1") (pintype "passive"))
      (node (ref "TEENSY_3.1") (pin "23/A9") (pinfunction "23/A9/T/PWM_23/A9") (pintype "bidirectional"))
    )
    (net (code "29") (name "CANH") (class "Default")
      (node (ref "C4") (pin "1") (pinfunction "1_1") (pintype "passive"))
      (node (ref "R34") (pin "2") (pinfunction "2_2") (pintype "passive"))
      (node (ref "SM24CANA") (pin "2") (pinfunction "A2_2") (pintype "passive"))
      (node (ref "U$3") (pin "P$10") (pinfunction "P$10_P$10") (pintype "bidirectional"))
      (node (ref "VP230") (pin "7") (pinfunction "CANH_7") (pintype "bidirectional"))
    )
    (net (code "30") (name "CANL") (class "Default")
      (node (ref "C5") (pin "2") (pinfunction "2_2") (pintype "passive"))
      (node (ref "R35") (pin "1") (pinfunction "1_1") (pintype "passive"))
      (node (ref "SM24CANA") (pin "1") (pinfunction "A1_1") (pintype "passive"))
      (node (ref "U$3") (pin "P$2") (pinfunction "P$2_P$2") (pintype "bidirectional"))
      (node (ref "VP230") (pin "6") (pinfunction "CANL_6") (pintype "bidirectional"))
    )
    (net (code "31") (name "CH2") (class "Default")
      (node (ref "F1") (pin "1") (pinfunction "1_1") (pintype "bidirectional"))
      (node (ref "Q14") (pin "3") (pinfunction "C_3") (pintype "passive"))
      (node (ref "Q5") (pin "4") (pinfunction "D_4") (pintype "passive"))
    )
    (net (code "32") (name "CH5") (class "Default")
      (node (ref "F2") (pin "1") (pinfunction "1_1") (pintype "bidirectional"))
      (node (ref "Q17") (pin "3") (pinfunction "C_3") (pintype "passive"))
      (node (ref "Q4") (pin "4") (pinfunction "D_4") (pintype "passive"))
    )
    (net (code "33") (name "CH6") (class "Default")
      (node (ref "Q18") (pin "3") (pinfunction "C_3") (pintype "passive"))
      (node (ref "Q6") (pin "4") (pinfunction "D_4") (pintype "passive"))
      (node (ref "U$2") (pin "P$1") (pinfunction "P$1_P$1") (pintype "bidirectional"))
    )
    (net (code "34") (name "FUSE1") (class "Default")
      (node (ref "F5") (pin "2") (pinfunction "2_2") (pintype "bidirectional"))
      (node (ref "U$3") (pin "P$20") (pinfunction "P$20_P$20") (pintype "bidirectional"))
    )
    (net (code "35") (name "FUSE2") (class "Default")
      (node (ref "F1") (pin "2") (pinfunction "2_2") (pintype "bidirectional"))
      (node (ref "U$3") (pin "P$9") (pinfunction "P$9_P$9") (pintype "bidirectional"))
    )
    (net (code "36") (name "FUSE3") (class "Default")
      (node (ref "F4") (pin "2") (pinfunction "2_2") (pintype "bidirectional"))
      (node (ref "SJ3") (pin "1") (pinfunction "1_1") (pintype "passive"))
      (node (ref "U$3") (pin "P$19") (pinfunction "P$19_P$19") (pintype "bidirectional"))
    )
    (net (code "37") (name "FUSE4") (class "Default")
      (node (ref "F3") (pin "2") (pinfunction "2_2") (pintype "bidirectional"))
      (node (ref "U$3") (pin "P$18") (pinfunction "P$18_P$18") (pintype "bidirectional"))
    )
    (net (code "38") (name "FUSE5") (class "Default")
      (node (ref "F2") (pin "2") (pinfunction "2_2") (pintype "bidirectional"))
      (node (ref "U$3") (pin "P$1") (pinfunction "P$1_P$1") (pintype "bidirectional"))
    )
    (net (code "39") (name "FUSE6") (class "Default")
      (node (ref "U$2") (pin "P$2") (pinfunction "P$2_P$2") (pintype "bidirectional"))
      (node (ref "U$3") (pin "P$17") (pinfunction "P$17_P$17") (pintype "bidirectional"))
    )
    (net (code "40") (name "FUSE7") (class "Default")
      (node (ref "F6") (pin "2") (pinfunction "2_2") (pintype "bidirectional"))
      (node (ref "SJ5") (pin "1") (pinfunction "1_1") (pintype "passive"))
      (node (ref "U$3") (pin "P$21") (pinfunction "P$21_P$21") (pintype "bidirectional"))
    )
    (net (code "41") (name "FUSE8") (class "Default")
      (node (ref "F7") (pin "2") (pinfunction "2_2") (pintype "bidirectional"))
      (node (ref "U$3") (pin "P$22") (pinfunction "P$22_P$22") (pintype "bidirectional"))
    )
    (net (code "42") (name "FUSE9") (class "Default")
      (node (ref "F8") (pin "2") (pinfunction "2_2") (pintype "bidirectional"))
      (node (ref "SJ1") (pin "1") (pinfunction "1_1") (pintype "passive"))
      (node (ref "U$3") (pin "P$23") (pinfunction "P$23_P$23") (pintype "bidirectional"))
    )
    (net (code "43") (name "FUSE10") (class "Default")
      (node (ref "F9") (pin "2") (pinfunction "2_2") (pintype "bidirectional"))
      (node (ref "U$3") (pin "P$8") (pinfunction "P$8_P$8") (pintype "bidirectional"))
    )
    (net (code "44") (name "FUSE11") (class "Default")
      (node (ref "F10") (pin "2") (pinfunction "2_2") (pintype "bidirectional"))
      (node (ref "U$3") (pin "P$16") (pinfunction "P$16_P$16") (pintype "bidirectional"))
    )
    (net (code "45") (name "FUSE12") (class "Default")
      (node (ref "F11") (pin "2") (pinfunction "2_2") (pintype "bidirectional"))
      (node (ref "U$3") (pin "P$24") (pinfunction "P$24_P$24") (pintype "bidirectional"))
    )
    (net (code "46") (name "GND") (class "Default")
      (node (ref "ATA6631") (pin "3") (pinfunction "GND_3") (pintype "bidirectional"))
      (node (ref "C10") (pin "2") (pinfunction "2_2") (pintype "passive"))
      (node (ref "C11") (pin "C") (pinfunction "-_C") (pintype "passive"))
      (node (ref "C12") (pin "2") (pinfunction "2_2") (pintype "passive"))
      (node (ref "C13") (pin "1") (pinfunction "1_1") (pintype "passive"))
      (node (ref "C14") (pin "2") (pinfunction "2_2") (pintype "passive"))
      (node (ref "C15") (pin "2") (pinfunction "2_2") (pintype "passive"))
      (node (ref "C16") (pin "1") (pinfunction "1_1") (pintype "passive"))
      (node (ref "C3") (pin "2") (pinfunction "2_2") (pintype "passive"))
      (node (ref "C4") (pin "2") (pinfunction "2_2") (pintype "passive"))
      (node (ref "C5") (pin "1") (pinfunction "1_1") (pintype "passive"))
      (node (ref "C6") (pin "1") (pinfunction "1_1") (pintype "passive"))
      (node (ref "C7") (pin "1") (pinfunction "1_1") (pintype "passive"))
      (node (ref "C8") (pin "2") (pinfunction "2_2") (pintype "passive"))
      (node (ref "C9") (pin "-") (pinfunction "-_-") (pintype "passive"))
      (node (ref "D2") (pin "A") (pinfunction "A_A") (pintype "passive"))
      (node (ref "R33") (pin "1") (pinfunction "1_1") (pintype "passive"))
      (node (ref "SM24CANA") (pin "3") (pinfunction "C_3") (pintype "passive"))
      (node (ref "T1") (pin "2") (pinfunction "E_2") (pintype "passive"))
      (node (ref "T10") (pin "2") (pinfunction "E_2") (pintype "passive"))
      (node (ref "T11") (pin "2") (pinfunction "E_2") (pintype "passive"))
      (node (ref "T12") (pin "2") (pinfunction "E_2") (pintype "passive"))
      (node (ref "T2") (pin "2") (pinfunction "E_2") (pintype "passive"))
      (node (ref "T3") (pin "2") (pinfunction "E_2") (pintype "passive"))
      (node (ref "T4") (pin "2") (pinfunction "E_2") (pintype "passive"))
      (node (ref "T5") (pin "2") (pinfunction "E_2") (pintype "passive"))
      (node (ref "T6") (pin "2") (pinfunction "E_2") (pintype "passive"))
      (node (ref "T7") (pin "2") (pinfunction "E_2") (pintype "passive"))
      (node (ref "T8") (pin "2") (pinfunction "E_2") (pintype "passive"))
      (node (ref "T9") (pin "2") (pinfunction "E_2") (pintype "passive"))
      (node (ref "TEENSY_3.1") (pin "AGND") (pinfunction "AGND_AGND") (pintype "power_in"))
      (node (ref "TEENSY_3.1") (pin "GND") (pinfunction "GND_GND") (pintype "power_in"))
      (node (ref "U$3") (pin "P$14") (pinfunction "P$14_P$14") (pintype "bidirectional"))
      (node (ref "U1") (pin "3") (pinfunction "3_3") (pintype "bidirectional"))
      (node (ref "U1") (pin "7") (pinfunction "7_7") (pintype "bidirectional"))
      (node (ref "VP230") (pin "2") (pinfunction "GND_2") (pintype "bidirectional"))
    )
    (net (code "47") (name "LINBUS") (class "Default")
      (node (ref "ATA6631") (pin "4") (pinfunction "LIN_4") (pintype "bidirectional"))
      (node (ref "C8") (pin "1") (pinfunction "1_1") (pintype "passive"))
      (node (ref "D2") (pin "C") (pinfunction "A1_C") (pintype "passive"))
      (node (ref "U$3") (pin "P$7") (pinfunction "P$7_P$7") (pintype "bidirectional"))
    )
    (net (code "48") (name "N$2") (class "Default")
      (node (ref "F9") (pin "1") (pinfunction "1_1") (pintype "bidirectional"))
      (node (ref "Q1") (pin "4") (pinfunction "D_4") (pintype "passive"))
      (node (ref "Q13") (pin "3") (pinfunction "C_3") (pintype "passive"))
    )
    (net (code "49") (name "N$10") (class "Default")
      (node (ref "F10") (pin "1") (pinfunction "1_1") (pintype "bidirectional"))
      (node (ref "Q15") (pin "3") (pinfunction "C_3") (pintype "passive"))
      (node (ref "Q2") (pin "4") (pinfunction "D_4") (pintype "passive"))
    )
    (net (code "50") (name "N$11") (class "Default")
      (node (ref "F11") (pin "1") (pinfunction "1_1") (pintype "bidirectional"))
      (node (ref "Q16") (pin "3") (pinfunction "C_3") (pintype "passive"))
      (node (ref "Q3") (pin "4") (pinfunction "D_4") (pintype "passive"))
    )
    (net (code "51") (name "N$19") (class "Default")
      (node (ref "Q1") (pin "1") (pinfunction "G_1") (pintype "passive"))
      (node (ref "Q13") (pin "1") (pinfunction "B_1") (pintype "passive"))
      (node (ref "R1") (pin "2") (pinfunction "2_2") (pintype "passive"))
      (node (ref "R2") (pin "1") (pinfunction "1_1") (pintype "passive"))
    )
    (net (code "52") (name "N$21") (class "Default")
      (node (ref "Q18") (pin "1") (pinfunction "B_1") (pintype "passive"))
      (node (ref "Q6") (pin "1") (pinfunction "G_1") (pintype "passive"))
      (node (ref "R11") (pin "2") (pinfunction "2_2") (pintype "passive"))
      (node (ref "R12") (pin "1") (pinfunction "1_1") (pintype "passive"))
    )
    (net (code "53") (name "N$25") (class "Default")
      (node (ref "Q15") (pin "1") (pinfunction "B_1") (pintype "passive"))
      (node (ref "Q2") (pin "1") (pinfunction "G_1") (pintype "passive"))
      (node (ref "R3") (pin "2") (pinfunction "2_2") (pintype "passive"))
      (node (ref "R4") (pin "1") (pinfunction "1_1") (pintype "passive"))
    )
    (net (code "54") (name "N$32") (class "Default")
      (node (ref "Q17") (pin "1") (pinfunction "B_1") (pintype "passive"))
      (node (ref "Q4") (pin "1") (pinfunction "G_1") (pintype "passive"))
      (node (ref "R7") (pin "2") (pinfunction "2_2") (pintype "passive"))
      (node (ref "R8") (pin "1") (pinfunction "1_1") (pintype "passive"))
    )
    (net (code "55") (name "N$40") (class "Default")
      (node (ref "Q16") (pin "1") (pinfunction "B_1") (pintype "passive"))
      (node (ref "Q3") (pin "1") (pinfunction "G_1") (pintype "passive"))
      (node (ref "R5") (pin "2") (pinfunction "2_2") (pintype "passive"))
      (node (ref "R6") (pin "1") (pinfunction "1_1") (pintype "passive"))
    )
    (net (code "56") (name "N$48") (class "Default")
      (node (ref "Q14") (pin "1") (pinfunction "B_1") (pintype "passive"))
      (node (ref "Q5") (pin "1") (pinfunction "G_1") (pintype "passive"))
      (node (ref "R10") (pin "1") (pinfunction "1_1") (pintype "passive"))
      (node (ref "R9") (pin "2") (pinfunction "2_2") (pintype "passive"))
    )
    (net (code "57") (name "Net-(ATA6631-NRES)") (class "Default")
      (node (ref "ATA6631") (pin "7") (pinfunction "NRES_7") (pintype "bidirectional"))
      (node (ref "R36") (pin "2") (pinfunction "2_2") (pintype "passive"))
    )
    (net (code "58") (name "Net-(ATA6631-VS)") (class "Default")
      (node (ref "ATA6631") (pin "1") (pinfunction "VS_1") (pintype "bidirectional"))
      (node (ref "C10") (pin "1") (pinfunction "1_1") (pintype "passive"))
      (node (ref "C9") (pin "+") (pinfunction "+_+") (pintype "passive"))
      (node (ref "GF1A") (pin "C") (pinfunction "C_C") (pintype "passive"))
    )
    (net (code "59") (name "Net-(C3-Pad1)") (class "Default")
      (node (ref "C3") (pin "1") (pinfunction "1_1") (pintype "passive"))
      (node (ref "R34") (pin "1") (pinfunction "1_1") (pintype "passive"))
      (node (ref "R35") (pin "2") (pinfunction "2_2") (pintype "passive"))
    )
    (net (code "60") (name "Net-(C13-Pad2)") (class "Default")
      (node (ref "C13") (pin "2") (pinfunction "2_2") (pintype "passive"))
      (node (ref "GF1A2") (pin "C") (pinfunction "C_C") (pintype "passive"))
      (node (ref "U1") (pin "1") (pinfunction "1_1") (pintype "bidirectional"))
    )
    (net (code "61") (name "Net-(C14-Pad1)") (class "Default")
      (node (ref "C14") (pin "1") (pinfunction "1_1") (pintype "passive"))
      (node (ref "GF1A3") (pin "C") (pinfunction "C_C") (pintype "passive"))
      (node (ref "U1") (pin "2") (pinfunction "2_2") (pintype "bidirectional"))
    )
    (net (code "62") (name "Net-(C15-Pad1)") (class "Default")
      (node (ref "C15") (pin "1") (pinfunction "1_1") (pintype "passive"))
      (node (ref "U1") (pin "5") (pinfunction "5_5") (pintype "bidirectional"))
    )
    (net (code "63") (name "Net-(Q7-B)") (class "Default")
      (node (ref "Q7") (pin "1") (pinfunction "B_1") (pintype "passive"))
      (node (ref "R13") (pin "2") (pinfunction "2_2") (pintype "passive"))
      (node (ref "R14") (pin "1") (pinfunction "1_1") (pintype "passive"))
    )
    (net (code "64") (name "Net-(Q7-C)") (class "Default")
      (node (ref "F6") (pin "1") (pinfunction "1_1") (pintype "bidirectional"))
      (node (ref "Q7") (pin "3") (pinfunction "C_3") (pintype "passive"))
    )
    (net (code "65") (name "Net-(Q8-B)") (class "Default")
      (node (ref "Q8") (pin "1") (pinfunction "B_1") (pintype "passive"))
      (node (ref "R15") (pin "2") (pinfunction "2_2") (pintype "passive"))
      (node (ref "R16") (pin "1") (pinfunction "1_1") (pintype "passive"))
    )
    (net (code "66") (name "Net-(Q8-C)") (class "Default")
      (node (ref "F7") (pin "1") (pinfunction "1_1") (pintype "bidirectional"))
      (node (ref "Q8") (pin "3") (pinfunction "C_3") (pintype "passive"))
    )
    (net (code "67") (name "Net-(Q9-B)") (class "Default")
      (node (ref "Q9") (pin "1") (pinfunction "B_1") (pintype "passive"))
      (node (ref "R17") (pin "2") (pinfunction "2_2") (pintype "passive"))
      (node (ref "R18") (pin "1") (pinfunction "1_1") (pintype "passive"))
    )
    (net (code "68") (name "Net-(Q9-C)") (class "Default")
      (node (ref "F8") (pin "1") (pinfunction "1_1") (pintype "bidirectional"))
      (node (ref "Q9") (pin "3") (pinfunction "C_3") (pintype "passive"))
    )
    (net (code "69") (name "Net-(Q10-B)") (class "Default")
      (node (ref "Q10") (pin "1") (pinfunction "B_1") (pintype "passive"))
      (node (ref "R19") (pin "2") (pinfunction "2_2") (pintype "passive"))
      (node (ref "R20") (pin "1") (pinfunction "1_1") (pintype "passive"))
    )
    (net (code "70") (name "Net-(Q10-C)") (class "Default")
      (node (ref "F5") (pin "1") (pinfunction "1_1") (pintype "bidirectional"))
      (node (ref "Q10") (pin "3") (pinfunction "C_3") (pintype "passive"))
    )
    (net (code "71") (name "Net-(Q11-B)") (class "Default")
      (node (ref "Q11") (pin "1") (pinfunction "B_1") (pintype "passive"))
      (node (ref "R21") (pin "2") (pinfunction "2_2") (pintype "passive"))
      (node (ref "R22") (pin "1") (pinfunction "1_1") (pintype "passive"))
    )
    (net (code "72") (name "Net-(Q11-C)") (class "Default")
      (node (ref "F4") (pin "1") (pinfunction "1_1") (pintype "bidirectional"))
      (node (ref "Q11") (pin "3") (pinfunction "C_3") (pintype "passive"))
    )
    (net (code "73") (name "Net-(Q12-B)") (class "Default")
      (node (ref "Q12") (pin "1") (pinfunction "B_1") (pintype "passive"))
      (node (ref "R23") (pin "2") (pinfunction "2_2") (pintype "passive"))
      (node (ref "R24") (pin "1") (pinfunction "1_1") (pintype "passive"))
    )
    (net (code "74") (name "Net-(Q12-C)") (class "Default")
      (node (ref "F3") (pin "1") (pinfunction "1_1") (pintype "bidirectional"))
      (node (ref "Q12") (pin "3") (pinfunction "C_3") (pintype "passive"))
    )
    (net (code "75") (name "Net-(R37-Pad1)") (class "Default")
      (node (ref "R37") (pin "1") (pinfunction "1_1") (pintype "passive"))
      (node (ref "U1") (pin "4") (pinfunction "4_4") (pintype "bidirectional"))
    )
    (net (code "76") (name "Net-(T1-C)") (class "Default")
      (node (ref "R19") (pin "1") (pinfunction "1_1") (pintype "passive"))
      (node (ref "T1") (pin "3") (pinfunction "C_3") (pintype "passive"))
    )
    (net (code "77") (name "Net-(T2-C)") (class "Default")
      (node (ref "R21") (pin "1") (pinfunction "1_1") (pintype "passive"))
      (node (ref "SJ3") (pin "2") (pinfunction "2_2") (pintype "passive"))
      (node (ref "T2") (pin "3") (pinfunction "C_3") (pintype "passive"))
    )
    (net (code "78") (name "Net-(T3-C)") (class "Default")
      (node (ref "R23") (pin "1") (pinfunction "1_1") (pintype "passive"))
      (node (ref "T3") (pin "3") (pinfunction "C_3") (pintype "passive"))
    )
    (net (code "79") (name "Net-(T4-C)") (class "Default")
      (node (ref "R7") (pin "1") (pinfunction "1_1") (pintype "passive"))
      (node (ref "T4") (pin "3") (pinfunction "C_3") (pintype "passive"))
    )
    (net (code "80") (name "Net-(T5-C)") (class "Default")
      (node (ref "R9") (pin "1") (pinfunction "1_1") (pintype "passive"))
      (node (ref "T5") (pin "3") (pinfunction "C_3") (pintype "passive"))
    )
    (net (code "81") (name "Net-(T6-C)") (class "Default")
      (node (ref "R11") (pin "1") (pinfunction "1_1") (pintype "passive"))
      (node (ref "T6") (pin "3") (pinfunction "C_3") (pintype "passive"))
    )
    (net (code "82") (name "Net-(T7-C)") (class "Default")
      (node (ref "R13") (pin "1") (pinfunction "1_1") (pintype "passive"))
      (node (ref "SJ5") (pin "2") (pinfunction "2_2") (pintype "passive"))
      (node (ref "T7") (pin "3") (pinfunction "C_3") (pintype "passive"))
    )
    (net (code "83") (name "Net-(T8-C)") (class "Default")
      (node (ref "R15") (pin "1") (pinfunction "1_1") (pintype "passive"))
      (node (ref "T8") (pin "3") (pinfunction "C_3") (pintype "passive"))
    )
    (net (code "84") (name "Net-(T9-C)") (class "Default")
      (node (ref "R17") (pin "1") (pinfunction "1_1") (pintype "passive"))
      (node (ref "SJ1") (pin "2") (pinfunction "2_2") (pintype "passive"))
      (node (ref "T9") (pin "3") (pinfunction "C_3") (pintype "passive"))
    )
    (net (code "85") (name "Net-(T10-C)") (class "Default")
      (node (ref "R1") (pin "1") (pinfunction "1_1") (pintype "passive"))
      (node (ref "T10") (pin "3") (pinfunction "C_3") (pintype "passive"))
    )
    (net (code "86") (name "Net-(T11-C)") (class "Default")
      (node (ref "R3") (pin "1") (pinfunction "1_1") (pintype "passive"))
      (node (ref "T11") (pin "3") (pinfunction "C_3") (pintype "passive"))
    )
    (net (code "87") (name "Net-(T12-C)") (class "Default")
      (node (ref "R5") (pin "1") (pinfunction "1_1") (pintype "passive"))
      (node (ref "T12") (pin "3") (pinfunction "C_3") (pintype "passive"))
    )
    (net (code "88") (name "Net-(VP230-RS)") (class "Default")
      (node (ref "R33") (pin "2") (pinfunction "2_2") (pintype "passive"))
      (node (ref "VP230") (pin "8") (pinfunction "RS_8") (pintype "bidirectional"))
    )
    (net (code "89") (name "Net-(VP230-VCC)") (class "Default")
      (node (ref "C6") (pin "2") (pinfunction "2_2") (pintype "passive"))
      (node (ref "C7") (pin "2") (pinfunction "2_2") (pintype "passive"))
      (node (ref "D1") (pin "C") (pinfunction "C_C") (pintype "passive"))
      (node (ref "VP230") (pin "3") (pinfunction "VCC_3") (pintype "bidirectional"))
    )
    (net (code "90") (name "TEMP") (class "Default")
      (node (ref "R38") (pin "1") (pinfunction "1_1") (pintype "passive"))
      (node (ref "U$3") (pin "P$13") (pinfunction "P$13_P$13") (pintype "bidirectional"))
    )
    (net (code "91") (name "unconnected-(VP230-VR-Pad5)") (class "Default")
      (node (ref "VP230") (pin "5") (pinfunction "VR_5") (pintype "bidirectional"))
    )
  )
)
